# rocket-mega-shield.net
KiCad netlist of a schematic drawn in EAGLE
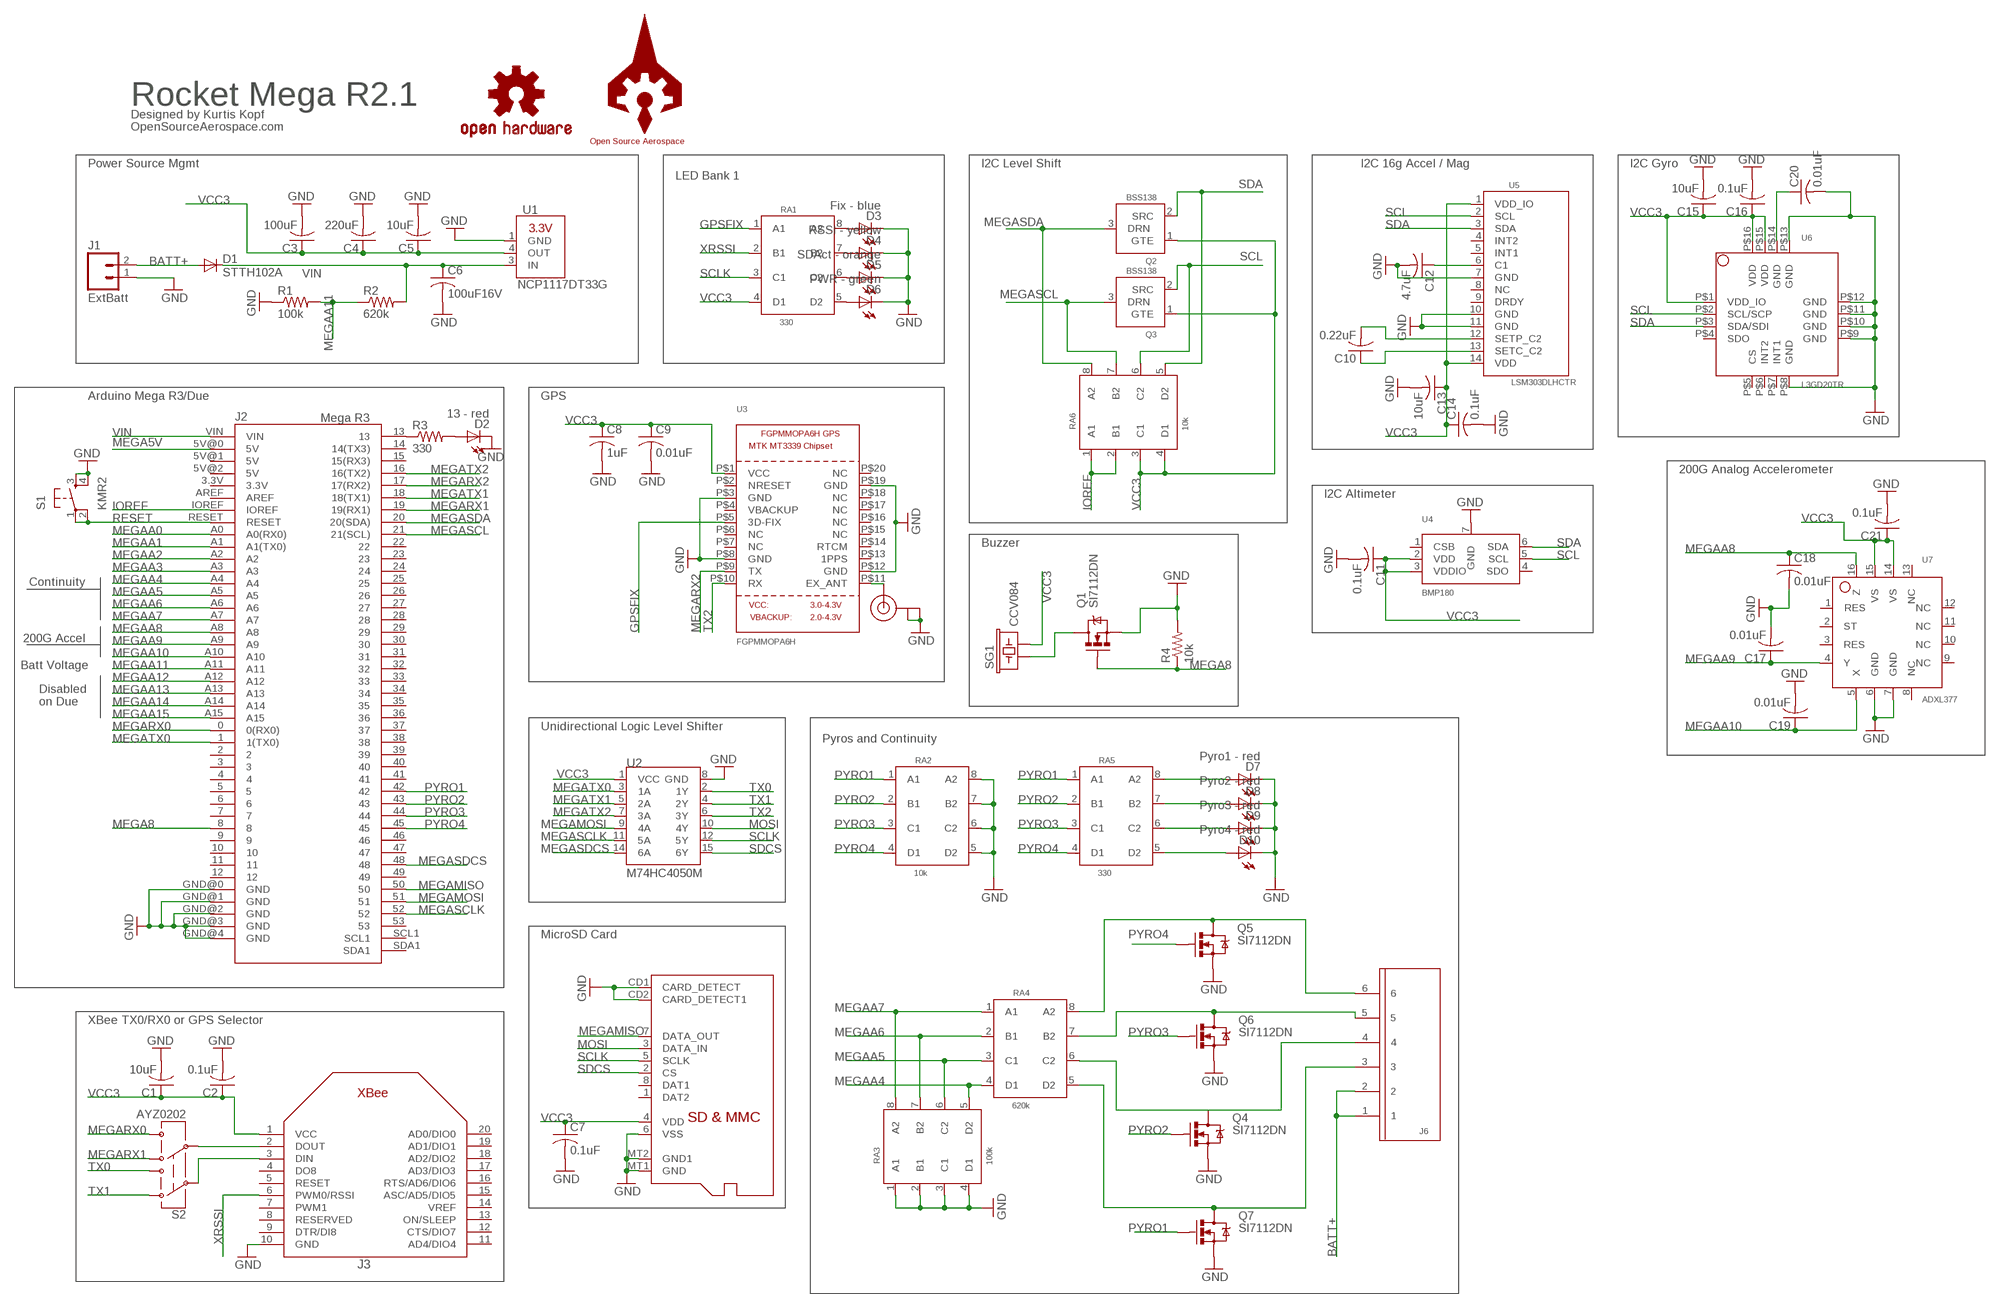
[diagram p0: schematic, sheet 1]

(export (version "E")
  (design (tool "Eeschema 10.0.6"))
  (components
    (comp (ref "C1")
      (value "10uF")
      (footprint "eagle-import:C1206")
      (libsource (lib "eagle-import") (part "C-USC1206"))
    )
    (comp (ref "C2")
      (value "0.1uF")
      (footprint "eagle-import:C1206")
      (libsource (lib "eagle-import") (part "C-USC1206"))
    )
    (comp (ref "C3")
      (value "100uF")
      (footprint "eagle-import:C1206")
      (libsource (lib "eagle-import") (part "C-USC1206"))
    )
    (comp (ref "C4")
      (value "220uF")
      (footprint "eagle-import:C1210")
      (libsource (lib "eagle-import") (part "C-USC1210"))
    )
    (comp (ref "C5")
      (value "10uF")
      (footprint "eagle-import:C1206")
      (libsource (lib "eagle-import") (part "C-USC1206"))
    )
    (comp (ref "C6")
      (value "100uF16V")
      (footprint "eagle-import:C1210")
      (libsource (lib "eagle-import") (part "C-USC1210"))
    )
    (comp (ref "C7")
      (value "0.1uF")
      (footprint "eagle-import:C1206")
      (libsource (lib "eagle-import") (part "C-USC1206"))
    )
    (comp (ref "C8")
      (value "1uF")
      (footprint "eagle-import:C1206")
      (libsource (lib "eagle-import") (part "C-USC1206"))
    )
    (comp (ref "C9")
      (value "0.01uF")
      (footprint "eagle-import:C1206")
      (libsource (lib "eagle-import") (part "C-USC1206"))
    )
    (comp (ref "C10")
      (value "0.22uF")
      (footprint "eagle-import:C1206")
      (libsource (lib "eagle-import") (part "C-USC1206"))
    )
    (comp (ref "C11")
      (value "0.1uF")
      (footprint "eagle-import:C1206")
      (libsource (lib "eagle-import") (part "C-USC1206"))
    )
    (comp (ref "C12")
      (value "4.7uF")
      (footprint "eagle-import:C1206")
      (libsource (lib "eagle-import") (part "C-USC1206"))
    )
    (comp (ref "C13")
      (value "10uF")
      (footprint "eagle-import:C1206")
      (libsource (lib "eagle-import") (part "C-USC1206"))
    )
    (comp (ref "C14")
      (value "0.1uF")
      (footprint "eagle-import:C1206")
      (libsource (lib "eagle-import") (part "C-USC1206"))
    )
    (comp (ref "C15")
      (value "10uF")
      (footprint "eagle-import:C1206")
      (libsource (lib "eagle-import") (part "C-USC1206"))
    )
    (comp (ref "C16")
      (value "0.1uF")
      (footprint "eagle-import:C1206")
      (libsource (lib "eagle-import") (part "C-USC1206"))
    )
    (comp (ref "C17")
      (value "0.01uF")
      (footprint "eagle-import:C1206")
      (libsource (lib "eagle-import") (part "C-USC1206"))
    )
    (comp (ref "C18")
      (value "0.01uF")
      (footprint "eagle-import:C1206")
      (libsource (lib "eagle-import") (part "C-USC1206"))
    )
    (comp (ref "C19")
      (value "0.01uF")
      (footprint "eagle-import:C1206")
      (libsource (lib "eagle-import") (part "C-USC1206"))
    )
    (comp (ref "C20")
      (value "0.01uF")
      (footprint "eagle-import:C1206")
      (libsource (lib "eagle-import") (part "C-USC1206"))
    )
    (comp (ref "C21")
      (value "0.1uF")
      (footprint "eagle-import:C1206")
      (libsource (lib "eagle-import") (part "C-USC1206"))
    )
    (comp (ref "D1")
      (value "STTH102A")
      (footprint "eagle-import:SMA-DIODE_ALT")
      (libsource (lib "eagle-import") (part "DIODESMA-ALT"))
    )
    (comp (ref "D2")
      (value "13 - red")
      (footprint "eagle-import:LED-1206")
      (libsource (lib "eagle-import") (part "LED1206"))
    )
    (comp (ref "D3")
      (value "Fix - blue")
      (footprint "eagle-import:LED-1206")
      (libsource (lib "eagle-import") (part "LED1206"))
    )
    (comp (ref "D4")
      (value "RSSI - yellow")
      (footprint "eagle-import:LED-1206")
      (libsource (lib "eagle-import") (part "LED1206"))
    )
    (comp (ref "D5")
      (value "SDAct - orange")
      (footprint "eagle-import:LED-1206")
      (libsource (lib "eagle-import") (part "LED1206"))
    )
    (comp (ref "D6")
      (value "PWR - green")
      (footprint "eagle-import:LED-1206")
      (libsource (lib "eagle-import") (part "LED1206"))
    )
    (comp (ref "D7")
      (value "Pyro1 - red")
      (footprint "eagle-import:LED-1206")
      (libsource (lib "eagle-import") (part "LED1206"))
    )
    (comp (ref "D8")
      (value "Pyro2 - red")
      (footprint "eagle-import:LED-1206")
      (libsource (lib "eagle-import") (part "LED1206"))
    )
    (comp (ref "D9")
      (value "Pyro3 - red")
      (footprint "eagle-import:LED-1206")
      (libsource (lib "eagle-import") (part "LED1206"))
    )
    (comp (ref "D10")
      (value "Pyro4 - red")
      (footprint "eagle-import:LED-1206")
      (libsource (lib "eagle-import") (part "LED1206"))
    )
    (comp (ref "J1")
      (value "ExtBatt")
      (footprint "eagle-import:JST-2-PTH-NS")
      (libsource (lib "eagle-import") (part "M02-JST-2-PTH-NO_SILK"))
    )
    (comp (ref "J2")
      (value "Mega R3")
      (footprint "eagle-import:ARDUINO_MEGA")
      (libsource (lib "eagle-import") (part "ARDUINO-MEGAFULL"))
    )
    (comp (ref "J3")
      (value "XBEE")
      (footprint "eagle-import:XBEE")
      (libsource (lib "eagle-import") (part "XBEE"))
    )
    (comp (ref "J4")
      (value "MICROSD")
      (footprint "eagle-import:MICROSD")
      (libsource (lib "eagle-import") (part "MICROSD"))
    )
    (comp (ref "J5")
      (value "U.FL")
      (footprint "eagle-import:U.FL")
      (libsource (lib "eagle-import") (part "U.FL"))
    )
    (comp (ref "J6")
      (value "1X6TERMINALBLOCK")
      (footprint "eagle-import:1X6TERMINALBLOCK")
      (libsource (lib "eagle-import") (part "1X6TERMINALBLOCK"))
    )
    (comp (ref "LOGO1")
      (value "OSHW-LOGOM")
      (footprint "eagle-import:OSHW-LOGO-M")
      (libsource (lib "eagle-import") (part "OSHW-LOGOM"))
    )
    (comp (ref "Q1")
      (value "SI7112DN")
      (footprint "eagle-import:POWERPAK1212-8")
      (libsource (lib "eagle-import") (part "MOSFET-NCHANNELSI7820DN"))
    )
    (comp (ref "Q2")
      (value "BSS138")
      (footprint "eagle-import:SOT23")
      (libsource (lib "eagle-import") (part "BSS138"))
    )
    (comp (ref "Q3")
      (value "BSS138")
      (footprint "eagle-import:SOT23")
      (libsource (lib "eagle-import") (part "BSS138"))
    )
    (comp (ref "Q4")
      (value "SI7112DN")
      (footprint "eagle-import:POWERPAK1212-8")
      (libsource (lib "eagle-import") (part "MOSFET-NCHANNELSI7820DN"))
    )
    (comp (ref "Q5")
      (value "SI7112DN")
      (footprint "eagle-import:POWERPAK1212-8")
      (libsource (lib "eagle-import") (part "MOSFET-NCHANNELSI7820DN"))
    )
    (comp (ref "Q6")
      (value "SI7112DN")
      (footprint "eagle-import:POWERPAK1212-8")
      (libsource (lib "eagle-import") (part "MOSFET-NCHANNELSI7820DN"))
    )
    (comp (ref "Q7")
      (value "SI7112DN")
      (footprint "eagle-import:POWERPAK1212-8")
      (libsource (lib "eagle-import") (part "MOSFET-NCHANNELSI7820DN"))
    )
    (comp (ref "R1")
      (value "100k")
      (footprint "eagle-import:R1206")
      (libsource (lib "eagle-import") (part "R-US_R1206"))
    )
    (comp (ref "R2")
      (value "620k")
      (footprint "eagle-import:R1206")
      (libsource (lib "eagle-import") (part "R-US_R1206"))
    )
    (comp (ref "R3")
      (value "330")
      (footprint "eagle-import:R1206")
      (libsource (lib "eagle-import") (part "R-US_R1206"))
    )
    (comp (ref "R4")
      (value "10k")
      (footprint "eagle-import:R1206")
      (libsource (lib "eagle-import") (part "R-US_R1206"))
    )
    (comp (ref "RA1")
      (value "330")
      (footprint "eagle-import:1206X4RESISTORARRAY")
      (libsource (lib "eagle-import") (part "RESISTOR_CRA06S08"))
    )
    (comp (ref "RA2")
      (value "10k")
      (footprint "eagle-import:1206X4RESISTORARRAY")
      (libsource (lib "eagle-import") (part "RESISTOR_CRA06S08"))
    )
    (comp (ref "RA3")
      (value "100k")
      (footprint "eagle-import:1206X4RESISTORARRAY")
      (libsource (lib "eagle-import") (part "RESISTOR_CRA06S08"))
    )
    (comp (ref "RA4")
      (value "620k")
      (footprint "eagle-import:1206X4RESISTORARRAY")
      (libsource (lib "eagle-import") (part "RESISTOR_CRA06S08"))
    )
    (comp (ref "RA5")
      (value "330")
      (footprint "eagle-import:1206X4RESISTORARRAY")
      (libsource (lib "eagle-import") (part "RESISTOR_CRA06S08"))
    )
    (comp (ref "RA6")
      (value "10k")
      (footprint "eagle-import:1206X4RESISTORARRAY")
      (libsource (lib "eagle-import") (part "RESISTOR_CRA06S08"))
    )
    (comp (ref "S1")
      (value "KMR2")
      (footprint "eagle-import:TACTILE_KMR2")
      (libsource (lib "eagle-import") (part "TAC_SWITCHKMR2"))
    )
    (comp (ref "S2")
      (value "AYZ0202")
      (footprint "eagle-import:AYZ0202")
      (libsource (lib "eagle-import") (part "AYZ0202"))
    )
    (comp (ref "SG1")
      (value "CCV084")
      (footprint "eagle-import:BUZZER-CCV")
      (libsource (lib "eagle-import") (part "BUZZERSMD2"))
    )
    (comp (ref "U$1")
      (value "OSAEROSPACEVECTOR")
      (footprint "eagle-import:OSAEROSPACE_V")
      (libsource (lib "eagle-import") (part "OSAEROSPACEVECTOR"))
    )
    (comp (ref "U1")
      (value "NCP1117DT33G")
      (footprint "eagle-import:DPAK")
      (libsource (lib "eagle-import") (part "NCP1117DT33G"))
    )
    (comp (ref "U2")
      (value "M74HC4050M")
      (footprint "eagle-import:SO016")
      (libsource (lib "eagle-import") (part "HEX_CONVERTER"))
    )
    (comp (ref "U3")
      (value "FGPMMOPA6H")
      (footprint "eagle-import:FGPMMOPA6H")
      (libsource (lib "eagle-import") (part "GPS_FGPMMOPA6H"))
    )
    (comp (ref "U4")
      (value "BMP180")
      (footprint "eagle-import:BMP180")
      (libsource (lib "eagle-import") (part "BMP180"))
    )
    (comp (ref "U5")
      (value "LSM303DLHCTR")
      (footprint "eagle-import:LGA14")
      (libsource (lib "eagle-import") (part "LSM303DLHC"))
    )
    (comp (ref "U6")
      (value "L3GD20TR")
      (footprint "eagle-import:LGA16-4X4")
      (libsource (lib "eagle-import") (part "L3GD20"))
    )
    (comp (ref "U7")
      (value "ADXL377")
      (footprint "eagle-import:LFCSP-16")
      (libsource (lib "eagle-import") (part "ADXL377"))
    )
  )
  (nets
    (net (code "1") (name "/BATT+") (class "Default")
      (node (ref "D1") (pin "A") (pinfunction "A_A") (pintype "passive"))
      (node (ref "J1") (pin "2") (pinfunction "2_2") (pintype "passive"))
      (node (ref "J6") (pin "1") (pinfunction "1_1") (pintype "bidirectional"))
      (node (ref "J6") (pin "2") (pinfunction "2_2") (pintype "bidirectional"))
    )
    (net (code "2") (name "/GPSFIX") (class "Default")
      (node (ref "RA1") (pin "1") (pinfunction "A1_1") (pintype "passive"))
      (node (ref "U3") (pin "P$5") (pinfunction "3D-FIX_P$5") (pintype "bidirectional"))
    )
    (net (code "3") (name "/IOREF") (class "Default")
      (node (ref "J2") (pin "IOREF") (pinfunction "IOREF_IOREF") (pintype "bidirectional"))
      (node (ref "RA6") (pin "1") (pinfunction "A1_1") (pintype "passive"))
      (node (ref "RA6") (pin "2") (pinfunction "B1_2") (pintype "passive"))
    )
    (net (code "4") (name "/MEGA5V") (class "Default")
      (node (ref "J2") (pin "5V@0") (pinfunction "5V_5V@0") (pintype "bidirectional"))
    )
    (net (code "5") (name "/MEGA8") (class "Default")
      (node (ref "J2") (pin "8") (pinfunction "8_8") (pintype "bidirectional"))
      (node (ref "Q1") (pin "G") (pinfunction "G_G") (pintype "passive"))
      (node (ref "R4") (pin "1") (pinfunction "1_1") (pintype "passive"))
    )
    (net (code "6") (name "/MEGAA0") (class "Default")
      (node (ref "J2") (pin "A0") (pinfunction "A0(RX0)_A0") (pintype "bidirectional"))
    )
    (net (code "7") (name "/MEGAA1") (class "Default")
      (node (ref "J2") (pin "A1") (pinfunction "A1(TX0)_A1") (pintype "bidirectional"))
    )
    (net (code "8") (name "/MEGAA2") (class "Default")
      (node (ref "J2") (pin "A2") (pinfunction "A2_A2") (pintype "bidirectional"))
    )
    (net (code "9") (name "/MEGAA3") (class "Default")
      (node (ref "J2") (pin "A3") (pinfunction "A3_A3") (pintype "bidirectional"))
    )
    (net (code "10") (name "/MEGAA4") (class "Default")
      (node (ref "J2") (pin "A4") (pinfunction "A4_A4") (pintype "bidirectional"))
      (node (ref "RA3") (pin "5") (pinfunction "D2_5") (pintype "passive"))
      (node (ref "RA4") (pin "4") (pinfunction "D1_4") (pintype "passive"))
    )
    (net (code "11") (name "/MEGAA5") (class "Default")
      (node (ref "J2") (pin "A5") (pinfunction "A5_A5") (pintype "bidirectional"))
      (node (ref "RA3") (pin "6") (pinfunction "C2_6") (pintype "passive"))
      (node (ref "RA4") (pin "3") (pinfunction "C1_3") (pintype "passive"))
    )
    (net (code "12") (name "/MEGAA6") (class "Default")
      (node (ref "J2") (pin "A6") (pinfunction "A6_A6") (pintype "bidirectional"))
      (node (ref "RA3") (pin "7") (pinfunction "B2_7") (pintype "passive"))
      (node (ref "RA4") (pin "2") (pinfunction "B1_2") (pintype "passive"))
    )
    (net (code "13") (name "/MEGAA7") (class "Default")
      (node (ref "J2") (pin "A7") (pinfunction "A7_A7") (pintype "bidirectional"))
      (node (ref "RA3") (pin "8") (pinfunction "A2_8") (pintype "passive"))
      (node (ref "RA4") (pin "1") (pinfunction "A1_1") (pintype "passive"))
    )
    (net (code "14") (name "/MEGAA8") (class "Default")
      (node (ref "C18") (pin "1") (pinfunction "1_1") (pintype "passive"))
      (node (ref "J2") (pin "A8") (pinfunction "A8_A8") (pintype "bidirectional"))
      (node (ref "U7") (pin "16") (pinfunction "Z_16") (pintype "output"))
    )
    (net (code "15") (name "/MEGAA9") (class "Default")
      (node (ref "C17") (pin "1") (pinfunction "1_1") (pintype "passive"))
      (node (ref "J2") (pin "A9") (pinfunction "A9_A9") (pintype "bidirectional"))
      (node (ref "U7") (pin "4") (pinfunction "Y_4") (pintype "output"))
    )
    (net (code "16") (name "/MEGAA10") (class "Default")
      (node (ref "C19") (pin "1") (pinfunction "1_1") (pintype "passive"))
      (node (ref "J2") (pin "A10") (pinfunction "A10_A10") (pintype "bidirectional"))
      (node (ref "U7") (pin "5") (pinfunction "X_5") (pintype "output"))
    )
    (net (code "17") (name "/MEGAA11") (class "Default")
      (node (ref "J2") (pin "A11") (pinfunction "A11_A11") (pintype "bidirectional"))
      (node (ref "R1") (pin "2") (pinfunction "2_2") (pintype "passive"))
      (node (ref "R2") (pin "1") (pinfunction "1_1") (pintype "passive"))
    )
    (net (code "18") (name "/MEGAA12") (class "Default")
      (node (ref "J2") (pin "A12") (pinfunction "A12_A12") (pintype "bidirectional"))
    )
    (net (code "19") (name "/MEGAA13") (class "Default")
      (node (ref "J2") (pin "A13") (pinfunction "A13_A13") (pintype "bidirectional"))
    )
    (net (code "20") (name "/MEGAA14") (class "Default")
      (node (ref "J2") (pin "A14") (pinfunction "A14_A14") (pintype "bidirectional"))
    )
    (net (code "21") (name "/MEGAA15") (class "Default")
      (node (ref "J2") (pin "A15") (pinfunction "A15_A15") (pintype "bidirectional"))
    )
    (net (code "22") (name "/MEGAMISO") (class "Default")
      (node (ref "J2") (pin "50") (pinfunction "50_50") (pintype "bidirectional"))
      (node (ref "J4") (pin "7") (pinfunction "DATA_OUT_7") (pintype "output"))
    )
    (net (code "23") (name "/MEGAMOSI") (class "Default")
      (node (ref "J2") (pin "51") (pinfunction "51_51") (pintype "bidirectional"))
      (node (ref "U2") (pin "9") (pinfunction "4A_9") (pintype "bidirectional"))
    )
    (net (code "24") (name "/MEGARX0") (class "Default")
      (node (ref "J2") (pin "0") (pinfunction "0(RX0)_0") (pintype "bidirectional"))
      (node (ref "S2") (pin "4") (pinfunction "6_4") (pintype "bidirectional"))
    )
    (net (code "25") (name "/MEGARX1") (class "Default")
      (node (ref "J2") (pin "19") (pinfunction "19(RX1)_19") (pintype "bidirectional"))
      (node (ref "S2") (pin "6") (pinfunction "4_6") (pintype "bidirectional"))
    )
    (net (code "26") (name "/MEGARX2") (class "Default")
      (node (ref "J2") (pin "17") (pinfunction "17(RX2)_17") (pintype "bidirectional"))
      (node (ref "U3") (pin "P$9") (pinfunction "TX_P$9") (pintype "bidirectional"))
    )
    (net (code "27") (name "/MEGASCL") (class "Default")
      (node (ref "J2") (pin "21") (pinfunction "21(SCL)_21") (pintype "bidirectional"))
      (node (ref "Q3") (pin "3") (pinfunction "DRN_3") (pintype "bidirectional"))
      (node (ref "RA6") (pin "7") (pinfunction "B2_7") (pintype "passive"))
    )
    (net (code "28") (name "/MEGASCLK") (class "Default")
      (node (ref "J2") (pin "52") (pinfunction "52_52") (pintype "bidirectional"))
      (node (ref "U2") (pin "11") (pinfunction "5A_11") (pintype "bidirectional"))
    )
    (net (code "29") (name "/MEGASDA") (class "Default")
      (node (ref "J2") (pin "20") (pinfunction "20(SDA)_20") (pintype "bidirectional"))
      (node (ref "Q2") (pin "3") (pinfunction "DRN_3") (pintype "bidirectional"))
      (node (ref "RA6") (pin "8") (pinfunction "A2_8") (pintype "passive"))
    )
    (net (code "30") (name "/MEGASDCS") (class "Default")
      (node (ref "J2") (pin "48") (pinfunction "48_48") (pintype "bidirectional"))
      (node (ref "U2") (pin "14") (pinfunction "6A_14") (pintype "bidirectional"))
    )
    (net (code "31") (name "/MEGATX0") (class "Default")
      (node (ref "J2") (pin "1") (pinfunction "1(TX0)_1") (pintype "bidirectional"))
      (node (ref "U2") (pin "3") (pinfunction "1A_3") (pintype "bidirectional"))
    )
    (net (code "32") (name "/MEGATX1") (class "Default")
      (node (ref "J2") (pin "18") (pinfunction "18(TX1)_18") (pintype "bidirectional"))
      (node (ref "U2") (pin "5") (pinfunction "2A_5") (pintype "bidirectional"))
    )
    (net (code "33") (name "/MEGATX2") (class "Default")
      (node (ref "J2") (pin "16") (pinfunction "16(TX2)_16") (pintype "bidirectional"))
      (node (ref "U2") (pin "7") (pinfunction "3A_7") (pintype "bidirectional"))
    )
    (net (code "34") (name "/MOSI") (class "Default")
      (node (ref "J4") (pin "3") (pinfunction "DATA_IN_3") (pintype "input"))
      (node (ref "U2") (pin "10") (pinfunction "4Y_10") (pintype "bidirectional"))
    )
    (net (code "35") (name "/PYRO1") (class "Default")
      (node (ref "J2") (pin "42") (pinfunction "42_42") (pintype "bidirectional"))
      (node (ref "Q7") (pin "G") (pinfunction "G_G") (pintype "passive"))
      (node (ref "RA2") (pin "1") (pinfunction "A1_1") (pintype "passive"))
      (node (ref "RA5") (pin "1") (pinfunction "A1_1") (pintype "passive"))
    )
    (net (code "36") (name "/PYRO2") (class "Default")
      (node (ref "J2") (pin "43") (pinfunction "43_43") (pintype "bidirectional"))
      (node (ref "Q4") (pin "G") (pinfunction "G_G") (pintype "passive"))
      (node (ref "RA2") (pin "2") (pinfunction "B1_2") (pintype "passive"))
      (node (ref "RA5") (pin "2") (pinfunction "B1_2") (pintype "passive"))
    )
    (net (code "37") (name "/PYRO3") (class "Default")
      (node (ref "J2") (pin "44") (pinfunction "44_44") (pintype "bidirectional"))
      (node (ref "Q6") (pin "G") (pinfunction "G_G") (pintype "passive"))
      (node (ref "RA2") (pin "3") (pinfunction "C1_3") (pintype "passive"))
      (node (ref "RA5") (pin "3") (pinfunction "C1_3") (pintype "passive"))
    )
    (net (code "38") (name "/PYRO4") (class "Default")
      (node (ref "J2") (pin "45") (pinfunction "45_45") (pintype "bidirectional"))
      (node (ref "Q5") (pin "G") (pinfunction "G_G") (pintype "passive"))
      (node (ref "RA2") (pin "4") (pinfunction "D1_4") (pintype "passive"))
      (node (ref "RA5") (pin "4") (pinfunction "D1_4") (pintype "passive"))
    )
    (net (code "39") (name "/RESET") (class "Default")
      (node (ref "J2") (pin "RESET") (pinfunction "RESET_RESET") (pintype "bidirectional"))
      (node (ref "S1") (pin "1") (pinfunction "1_1") (pintype "passive"))
      (node (ref "S1") (pin "2") (pinfunction "2_2") (pintype "passive"))
    )
    (net (code "40") (name "/SCL") (class "Default")
      (node (ref "Q3") (pin "2") (pinfunction "SRC_2") (pintype "bidirectional"))
      (node (ref "RA6") (pin "6") (pinfunction "C2_6") (pintype "passive"))
      (node (ref "U4") (pin "5") (pinfunction "SCL_5") (pintype "bidirectional"))
      (node (ref "U5") (pin "2") (pinfunction "SCL_2") (pintype "bidirectional"))
      (node (ref "U6") (pin "P$2") (pinfunction "SCL/SCP_P$2") (pintype "bidirectional"))
    )
    (net (code "41") (name "/SCLK") (class "Default")
      (node (ref "J4") (pin "5") (pinfunction "SCLK_5") (pintype "input"))
      (node (ref "RA1") (pin "3") (pinfunction "C1_3") (pintype "passive"))
      (node (ref "U2") (pin "12") (pinfunction "5Y_12") (pintype "bidirectional"))
    )
    (net (code "42") (name "/SDA") (class "Default")
      (node (ref "Q2") (pin "2") (pinfunction "SRC_2") (pintype "bidirectional"))
      (node (ref "RA6") (pin "5") (pinfunction "D2_5") (pintype "passive"))
      (node (ref "U4") (pin "6") (pinfunction "SDA_6") (pintype "bidirectional"))
      (node (ref "U5") (pin "3") (pinfunction "SDA_3") (pintype "bidirectional"))
      (node (ref "U6") (pin "P$3") (pinfunction "SDA/SDI_P$3") (pintype "bidirectional"))
    )
    (net (code "43") (name "/SDCS") (class "Default")
      (node (ref "J4") (pin "2") (pinfunction "CS_2") (pintype "input"))
      (node (ref "U2") (pin "15") (pinfunction "6Y_15") (pintype "bidirectional"))
    )
    (net (code "44") (name "/TX0") (class "Default")
      (node (ref "S2") (pin "1") (pinfunction "3_1") (pintype "bidirectional"))
      (node (ref "U2") (pin "2") (pinfunction "1Y_2") (pintype "bidirectional"))
    )
    (net (code "45") (name "/TX1") (class "Default")
      (node (ref "S2") (pin "3") (pinfunction "1_3") (pintype "bidirectional"))
      (node (ref "U2") (pin "4") (pinfunction "2Y_4") (pintype "bidirectional"))
    )
    (net (code "46") (name "/TX2") (class "Default")
      (node (ref "U2") (pin "6") (pinfunction "3Y_6") (pintype "bidirectional"))
      (node (ref "U3") (pin "P$10") (pinfunction "RX_P$10") (pintype "bidirectional"))
    )
    (net (code "47") (name "/VCC3") (class "Default")
      (node (ref "C1") (pin "1") (pinfunction "1_1") (pintype "passive"))
      (node (ref "C11") (pin "1") (pinfunction "1_1") (pintype "passive"))
      (node (ref "C13") (pin "1") (pinfunction "1_1") (pintype "passive"))
      (node (ref "C14") (pin "1") (pinfunction "1_1") (pintype "passive"))
      (node (ref "C15") (pin "1") (pinfunction "1_1") (pintype "passive"))
      (node (ref "C16") (pin "1") (pinfunction "1_1") (pintype "passive"))
      (node (ref "C2") (pin "1") (pinfunction "1_1") (pintype "passive"))
      (node (ref "C21") (pin "1") (pinfunction "1_1") (pintype "passive"))
      (node (ref "C3") (pin "1") (pinfunction "1_1") (pintype "passive"))
      (node (ref "C4") (pin "1") (pinfunction "1_1") (pintype "passive"))
      (node (ref "C5") (pin "1") (pinfunction "1_1") (pintype "passive"))
      (node (ref "C7") (pin "1") (pinfunction "1_1") (pintype "passive"))
      (node (ref "C8") (pin "1") (pinfunction "1_1") (pintype "passive"))
      (node (ref "C9") (pin "1") (pinfunction "1_1") (pintype "passive"))
      (node (ref "J3") (pin "1") (pinfunction "VCC_1") (pintype "power_in"))
      (node (ref "J4") (pin "4") (pinfunction "VDD_4") (pintype "power_in"))
      (node (ref "Q2") (pin "1") (pinfunction "GTE_1") (pintype "bidirectional"))
      (node (ref "Q3") (pin "1") (pinfunction "GTE_1") (pintype "bidirectional"))
      (node (ref "RA1") (pin "4") (pinfunction "D1_4") (pintype "passive"))
      (node (ref "RA6") (pin "3") (pinfunction "C1_3") (pintype "passive"))
      (node (ref "RA6") (pin "4") (pinfunction "D1_4") (pintype "passive"))
      (node (ref "SG1") (pin "-") (pinfunction "2_-") (pintype "passive"))
      (node (ref "U1") (pin "4") (pinfunction "OUT_4") (pintype "power_in"))
      (node (ref "U2") (pin "1") (pinfunction "VCC_1") (pintype "bidirectional"))
      (node (ref "U3") (pin "P$1") (pinfunction "VCC_P$1") (pintype "bidirectional"))
      (node (ref "U4") (pin "2") (pinfunction "VDD_2") (pintype "power_in"))
      (node (ref "U4") (pin "3") (pinfunction "VDDIO_3") (pintype "power_in"))
      (node (ref "U5") (pin "1") (pinfunction "VDD_IO_1") (pintype "power_in"))
      (node (ref "U5") (pin "14") (pinfunction "VDD_14") (pintype "power_in"))
      (node (ref "U6") (pin "P$1") (pinfunction "VDD_IO_P$1") (pintype "power_in"))
      (node (ref "U6") (pin "P$15") (pinfunction "VDD_P$15") (pintype "power_in"))
      (node (ref "U6") (pin "P$16") (pinfunction "VDD_P$16") (pintype "power_in"))
      (node (ref "U7") (pin "14") (pinfunction "VS_14") (pintype "power_in"))
      (node (ref "U7") (pin "15") (pinfunction "VS_15") (pintype "power_in"))
    )
    (net (code "48") (name "/VIN") (class "Default")
      (node (ref "C6") (pin "1") (pinfunction "1_1") (pintype "passive"))
      (node (ref "D1") (pin "C") (pinfunction "C_C") (pintype "passive"))
      (node (ref "J2") (pin "VIN") (pinfunction "VIN_VIN") (pintype "bidirectional"))
      (node (ref "R2") (pin "2") (pinfunction "2_2") (pintype "passive"))
      (node (ref "U1") (pin "3") (pinfunction "IN_3") (pintype "power_in"))
    )
    (net (code "49") (name "/XRSSI") (class "Default")
      (node (ref "J3") (pin "6") (pinfunction "PWM0/RSSI_6") (pintype "output"))
      (node (ref "RA1") (pin "2") (pinfunction "B1_2") (pintype "passive"))
    )
    (net (code "50") (name "GND") (class "Default")
      (node (ref "C1") (pin "2") (pinfunction "2_2") (pintype "passive"))
      (node (ref "C11") (pin "2") (pinfunction "2_2") (pintype "passive"))
      (node (ref "C12") (pin "2") (pinfunction "2_2") (pintype "passive"))
      (node (ref "C13") (pin "2") (pinfunction "2_2") (pintype "passive"))
      (node (ref "C14") (pin "2") (pinfunction "2_2") (pintype "passive"))
      (node (ref "C15") (pin "2") (pinfunction "2_2") (pintype "passive"))
      (node (ref "C16") (pin "2") (pinfunction "2_2") (pintype "passive"))
      (node (ref "C17") (pin "2") (pinfunction "2_2") (pintype "passive"))
      (node (ref "C18") (pin "2") (pinfunction "2_2") (pintype "passive"))
      (node (ref "C19") (pin "2") (pinfunction "2_2") (pintype "passive"))
      (node (ref "C2") (pin "2") (pinfunction "2_2") (pintype "passive"))
      (node (ref "C20") (pin "2") (pinfunction "2_2") (pintype "passive"))
      (node (ref "C21") (pin "2") (pinfunction "2_2") (pintype "passive"))
      (node (ref "C3") (pin "2") (pinfunction "2_2") (pintype "passive"))
      (node (ref "C4") (pin "2") (pinfunction "2_2") (pintype "passive"))
      (node (ref "C5") (pin "2") (pinfunction "2_2") (pintype "passive"))
      (node (ref "C6") (pin "2") (pinfunction "2_2") (pintype "passive"))
      (node (ref "C7") (pin "2") (pinfunction "2_2") (pintype "passive"))
      (node (ref "C8") (pin "2") (pinfunction "2_2") (pintype "passive"))
      (node (ref "C9") (pin "2") (pinfunction "2_2") (pintype "passive"))
      (node (ref "D10") (pin "C") (pinfunction "C_C") (pintype "passive"))
      (node (ref "D2") (pin "C") (pinfunction "C_C") (pintype "passive"))
      (node (ref "D3") (pin "C") (pinfunction "C_C") (pintype "passive"))
      (node (ref "D4") (pin "C") (pinfunction "C_C") (pintype "passive"))
      (node (ref "D5") (pin "C") (pinfunction "C_C") (pintype "passive"))
      (node (ref "D6") (pin "C") (pinfunction "C_C") (pintype "passive"))
      (node (ref "D7") (pin "C") (pinfunction "C_C") (pintype "passive"))
      (node (ref "D8") (pin "C") (pinfunction "C_C") (pintype "passive"))
      (node (ref "D9") (pin "C") (pinfunction "C_C") (pintype "passive"))
      (node (ref "J1") (pin "1") (pinfunction "1_1") (pintype "passive"))
      (node (ref "J2") (pin "GND@0") (pinfunction "GND_GND@0") (pintype "bidirectional"))
      (node (ref "J2") (pin "GND@1") (pinfunction "GND_GND@1") (pintype "bidirectional"))
      (node (ref "J2") (pin "GND@2") (pinfunction "GND_GND@2") (pintype "bidirectional"))
      (node (ref "J2") (pin "GND@3") (pinfunction "GND_GND@3") (pintype "bidirectional"))
      (node (ref "J2") (pin "GND@4") (pinfunction "GND_GND@4") (pintype "bidirectional"))
      (node (ref "J3") (pin "10") (pinfunction "GND_10") (pintype "power_in"))
      (node (ref "J4") (pin "6") (pinfunction "VSS_6") (pintype "power_in"))
      (node (ref "J4") (pin "CD1") (pinfunction "CARD_DETECT_CD1") (pintype "passive"))
      (node (ref "J4") (pin "CD2") (pinfunction "CARD_DETECT1_CD2") (pintype "passive"))
      (node (ref "J4") (pin "MT1") (pinfunction "GND_MT1") (pintype "power_in"))
      (node (ref "J4") (pin "MT2") (pinfunction "GND1_MT2") (pintype "power_in"))
      (node (ref "J5") (pin "P$1") (pinfunction "GND_P$1") (pintype "bidirectional"))
      (node (ref "J5") (pin "P$2") (pinfunction "GND_P$2") (pintype "bidirectional"))
      (node (ref "Q1") (pin "S1") (pinfunction "S_S1") (pintype "passive"))
      (node (ref "Q1") (pin "S2") (pinfunction "S_S2") (pintype "passive"))
      (node (ref "Q1") (pin "S3") (pinfunction "S_S3") (pintype "passive"))
      (node (ref "Q4") (pin "S1") (pinfunction "S_S1") (pintype "passive"))
      (node (ref "Q4") (pin "S2") (pinfunction "S_S2") (pintype "passive"))
      (node (ref "Q4") (pin "S3") (pinfunction "S_S3") (pintype "passive"))
      (node (ref "Q5") (pin "S1") (pinfunction "S_S1") (pintype "passive"))
      (node (ref "Q5") (pin "S2") (pinfunction "S_S2") (pintype "passive"))
      (node (ref "Q5") (pin "S3") (pinfunction "S_S3") (pintype "passive"))
      (node (ref "Q6") (pin "S1") (pinfunction "S_S1") (pintype "passive"))
      (node (ref "Q6") (pin "S2") (pinfunction "S_S2") (pintype "passive"))
      (node (ref "Q6") (pin "S3") (pinfunction "S_S3") (pintype "passive"))
      (node (ref "Q7") (pin "S1") (pinfunction "S_S1") (pintype "passive"))
      (node (ref "Q7") (pin "S2") (pinfunction "S_S2") (pintype "passive"))
      (node (ref "Q7") (pin "S3") (pinfunction "S_S3") (pintype "passive"))
      (node (ref "R1") (pin "1") (pinfunction "1_1") (pintype "passive"))
      (node (ref "R4") (pin "2") (pinfunction "2_2") (pintype "passive"))
      (node (ref "RA2") (pin "5") (pinfunction "D2_5") (pintype "passive"))
      (node (ref "RA2") (pin "6") (pinfunction "C2_6") (pintype "passive"))
      (node (ref "RA2") (pin "7") (pinfunction "B2_7") (pintype "passive"))
      (node (ref "RA2") (pin "8") (pinfunction "A2_8") (pintype "passive"))
      (node (ref "RA3") (pin "1") (pinfunction "A1_1") (pintype "passive"))
      (node (ref "RA3") (pin "2") (pinfunction "B1_2") (pintype "passive"))
      (node (ref "RA3") (pin "3") (pinfunction "C1_3") (pintype "passive"))
      (node (ref "RA3") (pin "4") (pinfunction "D1_4") (pintype "passive"))
      (node (ref "S1") (pin "3") (pinfunction "3_3") (pintype "passive"))
      (node (ref "S1") (pin "4") (pinfunction "4_4") (pintype "passive"))
      (node (ref "U1") (pin "1") (pinfunction "GND_1") (pintype "power_in"))
      (node (ref "U2") (pin "8") (pinfunction "GND_8") (pintype "bidirectional"))
      (node (ref "U3") (pin "P$12") (pinfunction "GND_P$12") (pintype "bidirectional"))
      (node (ref "U3") (pin "P$19") (pinfunction "GND_P$19") (pintype "bidirectional"))
      (node (ref "U3") (pin "P$3") (pinfunction "GND_P$3") (pintype "bidirectional"))
      (node (ref "U3") (pin "P$8") (pinfunction "GND_P$8") (pintype "bidirectional"))
      (node (ref "U4") (pin "7") (pinfunction "GND_7") (pintype "power_in"))
      (node (ref "U5") (pin "10") (pinfunction "GND_10") (pintype "power_in"))
      (node (ref "U5") (pin "11") (pinfunction "GND_11") (pintype "power_in"))
      (node (ref "U5") (pin "7") (pinfunction "GND_7") (pintype "power_in"))
      (node (ref "U6") (pin "P$10") (pinfunction "GND_P$10") (pintype "power_in"))
      (node (ref "U6") (pin "P$11") (pinfunction "GND_P$11") (pintype "power_in"))
      (node (ref "U6") (pin "P$12") (pinfunction "GND_P$12") (pintype "power_in"))
      (node (ref "U6") (pin "P$13") (pinfunction "GND_P$13") (pintype "power_in"))
      (node (ref "U6") (pin "P$8") (pinfunction "GND_P$8") (pintype "power_in"))
      (node (ref "U6") (pin "P$9") (pinfunction "GND_P$9") (pintype "power_in"))
      (node (ref "U7") (pin "6") (pinfunction "GND_6") (pintype "power_in"))
      (node (ref "U7") (pin "7") (pinfunction "GND_7") (pintype "power_in"))
    )
    (net (code "51") (name "Net-(C20-Pad1)") (class "Default")
      (node (ref "C20") (pin "1") (pinfunction "1_1") (pintype "passive"))
      (node (ref "U6") (pin "P$14") (pinfunction "GND_P$14") (pintype "power_in"))
    )
    (net (code "52") (name "Net-(D2-PadA)") (class "Default")
      (node (ref "D2") (pin "A") (pinfunction "A_A") (pintype "passive"))
      (node (ref "R3") (pin "2") (pinfunction "2_2") (pintype "passive"))
    )
    (net (code "53") (name "Net-(J2-Pad13)") (class "Default")
      (node (ref "J2") (pin "13") (pinfunction "13_13") (pintype "bidirectional"))
      (node (ref "R3") (pin "1") (pinfunction "1_1") (pintype "passive"))
    )
    (net (code "54") (name "Net-(J3-DIN)") (class "Default")
      (node (ref "J3") (pin "3") (pinfunction "DIN_3") (pintype "input"))
      (node (ref "S2") (pin "2") (pinfunction "2_2") (pintype "bidirectional"))
    )
    (net (code "55") (name "Net-(J3-DOUT)") (class "Default")
      (node (ref "J3") (pin "2") (pinfunction "DOUT_2") (pintype "output"))
      (node (ref "S2") (pin "5") (pinfunction "5_5") (pintype "bidirectional"))
    )
    (net (code "56") (name "Net-(J5-SIGNAL)") (class "Default")
      (node (ref "J5") (pin "P$3") (pinfunction "SIGNAL_P$3") (pintype "bidirectional"))
      (node (ref "U3") (pin "P$11") (pinfunction "EX_ANT_P$11") (pintype "bidirectional"))
    )
    (net (code "57") (name "Net-(RA1-A2)") (class "Default")
      (node (ref "D3") (pin "A") (pinfunction "A_A") (pintype "passive"))
      (node (ref "RA1") (pin "8") (pinfunction "A2_8") (pintype "passive"))
    )
    (net (code "58") (name "Net-(RA1-B2)") (class "Default")
      (node (ref "D4") (pin "A") (pinfunction "A_A") (pintype "passive"))
      (node (ref "RA1") (pin "7") (pinfunction "B2_7") (pintype "passive"))
    )
    (net (code "59") (name "Net-(RA1-C2)") (class "Default")
      (node (ref "D5") (pin "A") (pinfunction "A_A") (pintype "passive"))
      (node (ref "RA1") (pin "6") (pinfunction "C2_6") (pintype "passive"))
    )
    (net (code "60") (name "Net-(RA1-D2)") (class "Default")
      (node (ref "D6") (pin "A") (pinfunction "A_A") (pintype "passive"))
      (node (ref "RA1") (pin "5") (pinfunction "D2_5") (pintype "passive"))
    )
    (net (code "61") (name "Net-(RA4-A2)") (class "Default")
      (node (ref "J6") (pin "6") (pinfunction "6_6") (pintype "bidirectional"))
      (node (ref "Q5") (pin "D1") (pinfunction "D_D1") (pintype "passive"))
      (node (ref "Q5") (pin "D2") (pinfunction "D_D2") (pintype "passive"))
      (node (ref "Q5") (pin "D3") (pinfunction "D_D3") (pintype "passive"))
      (node (ref "Q5") (pin "D4") (pinfunction "D_D4") (pintype "passive"))
      (node (ref "Q5") (pin "DPAD") (pinfunction "D_DPAD") (pintype "passive"))
      (node (ref "RA4") (pin "8") (pinfunction "A2_8") (pintype "passive"))
    )
    (net (code "62") (name "Net-(RA4-B2)") (class "Default")
      (node (ref "J6") (pin "5") (pinfunction "5_5") (pintype "bidirectional"))
      (node (ref "Q6") (pin "D1") (pinfunction "D_D1") (pintype "passive"))
      (node (ref "Q6") (pin "D2") (pinfunction "D_D2") (pintype "passive"))
      (node (ref "Q6") (pin "D3") (pinfunction "D_D3") (pintype "passive"))
      (node (ref "Q6") (pin "D4") (pinfunction "D_D4") (pintype "passive"))
      (node (ref "Q6") (pin "DPAD") (pinfunction "D_DPAD") (pintype "passive"))
      (node (ref "RA4") (pin "7") (pinfunction "B2_7") (pintype "passive"))
    )
    (net (code "63") (name "Net-(RA4-C2)") (class "Default")
      (node (ref "J6") (pin "4") (pinfunction "4_4") (pintype "bidirectional"))
      (node (ref "Q4") (pin "D1") (pinfunction "D_D1") (pintype "passive"))
      (node (ref "Q4") (pin "D2") (pinfunction "D_D2") (pintype "passive"))
      (node (ref "Q4") (pin "D3") (pinfunction "D_D3") (pintype "passive"))
      (node (ref "Q4") (pin "D4") (pinfunction "D_D4") (pintype "passive"))
      (node (ref "Q4") (pin "DPAD") (pinfunction "D_DPAD") (pintype "passive"))
      (node (ref "RA4") (pin "6") (pinfunction "C2_6") (pintype "passive"))
    )
    (net (code "64") (name "Net-(RA4-D2)") (class "Default")
      (node (ref "J6") (pin "3") (pinfunction "3_3") (pintype "bidirectional"))
      (node (ref "Q7") (pin "D1") (pinfunction "D_D1") (pintype "passive"))
      (node (ref "Q7") (pin "D2") (pinfunction "D_D2") (pintype "passive"))
      (node (ref "Q7") (pin "D3") (pinfunction "D_D3") (pintype "passive"))
      (node (ref "Q7") (pin "D4") (pinfunction "D_D4") (pintype "passive"))
      (node (ref "Q7") (pin "DPAD") (pinfunction "D_DPAD") (pintype "passive"))
      (node (ref "RA4") (pin "5") (pinfunction "D2_5") (pintype "passive"))
    )
    (net (code "65") (name "Net-(RA5-A2)") (class "Default")
      (node (ref "D7") (pin "A") (pinfunction "A_A") (pintype "passive"))
      (node (ref "RA5") (pin "8") (pinfunction "A2_8") (pintype "passive"))
    )
    (net (code "66") (name "Net-(RA5-B2)") (class "Default")
      (node (ref "D8") (pin "A") (pinfunction "A_A") (pintype "passive"))
      (node (ref "RA5") (pin "7") (pinfunction "B2_7") (pintype "passive"))
    )
    (net (code "67") (name "Net-(RA5-C2)") (class "Default")
      (node (ref "D9") (pin "A") (pinfunction "A_A") (pintype "passive"))
      (node (ref "RA5") (pin "6") (pinfunction "C2_6") (pintype "passive"))
    )
    (net (code "68") (name "Net-(RA5-D2)") (class "Default")
      (node (ref "D10") (pin "A") (pinfunction "A_A") (pintype "passive"))
      (node (ref "RA5") (pin "5") (pinfunction "D2_5") (pintype "passive"))
    )
    (net (code "69") (name "Net-(SG1-1)") (class "Default")
      (node (ref "Q1") (pin "D1") (pinfunction "D_D1") (pintype "passive"))
      (node (ref "Q1") (pin "D2") (pinfunction "D_D2") (pintype "passive"))
      (node (ref "Q1") (pin "D3") (pinfunction "D_D3") (pintype "passive"))
      (node (ref "Q1") (pin "D4") (pinfunction "D_D4") (pintype "passive"))
      (node (ref "Q1") (pin "DPAD") (pinfunction "D_DPAD") (pintype "passive"))
      (node (ref "SG1") (pin "+") (pinfunction "1_+") (pintype "passive"))
    )
    (net (code "70") (name "Net-(U5-C1)") (class "Default")
      (node (ref "C12") (pin "1") (pinfunction "1_1") (pintype "passive"))
      (node (ref "U5") (pin "6") (pinfunction "C1_6") (pintype "passive"))
    )
    (net (code "71") (name "Net-(U5-SETC_C2)") (class "Default")
      (node (ref "C10") (pin "1") (pinfunction "1_1") (pintype "passive"))
      (node (ref "U5") (pin "13") (pinfunction "SETC_C2_13") (pintype "passive"))
    )
    (net (code "72") (name "Net-(U5-SETP_C2)") (class "Default")
      (node (ref "C10") (pin "2") (pinfunction "2_2") (pintype "passive"))
      (node (ref "U5") (pin "12") (pinfunction "SETP_C2_12") (pintype "passive"))
    )
    (net (code "73") (name "unconnected-(J2-5V-Pad5V@1)") (class "Default")
      (node (ref "J2") (pin "5V@1") (pinfunction "5V_5V@1") (pintype "bidirectional"))
    )
    (net (code "74") (name "unconnected-(J2-5V-Pad5V@2)") (class "Default")
      (node (ref "J2") (pin "5V@2") (pinfunction "5V_5V@2") (pintype "bidirectional"))
    )
    (net (code "75") (name "unconnected-(J2-14(TX3)-Pad14)") (class "Default")
      (node (ref "J2") (pin "14") (pinfunction "14(TX3)_14") (pintype "bidirectional"))
    )
    (net (code "76") (name "unconnected-(J2-15(RX3)-Pad15)") (class "Default")
      (node (ref "J2") (pin "15") (pinfunction "15(RX3)_15") (pintype "bidirectional"))
    )
    (net (code "77") (name "unconnected-(J2-Pad2)") (class "Default")
      (node (ref "J2") (pin "2") (pinfunction "2_2") (pintype "bidirectional"))
    )
    (net (code "78") (name "unconnected-(J2-Pad3)") (class "Default")
      (node (ref "J2") (pin "3") (pinfunction "3_3") (pintype "bidirectional"))
    )
    (net (code "79") (name "unconnected-(J2-Pad3.3V)") (class "Default")
      (node (ref "J2") (pin "3.3V") (pinfunction "3.3V_3.3V") (pintype "bidirectional"))
    )
    (net (code "80") (name "unconnected-(J2-Pad4)") (class "Default")
      (node (ref "J2") (pin "4") (pinfunction "4_4") (pintype "bidirectional"))
    )
    (net (code "81") (name "unconnected-(J2-Pad5)") (class "Default")
      (node (ref "J2") (pin "5") (pinfunction "5_5") (pintype "bidirectional"))
    )
    (net (code "82") (name "unconnected-(J2-Pad6)") (class "Default")
      (node (ref "J2") (pin "6") (pinfunction "6_6") (pintype "bidirectional"))
    )
    (net (code "83") (name "unconnected-(J2-Pad7)") (class "Default")
      (node (ref "J2") (pin "7") (pinfunction "7_7") (pintype "bidirectional"))
    )
    (net (code "84") (name "unconnected-(J2-Pad9)") (class "Default")
      (node (ref "J2") (pin "9") (pinfunction "9_9") (pintype "bidirectional"))
    )
    (net (code "85") (name "unconnected-(J2-Pad10)") (class "Default")
      (node (ref "J2") (pin "10") (pinfunction "10_10") (pintype "bidirectional"))
    )
    (net (code "86") (name "unconnected-(J2-Pad11)") (class "Default")
      (node (ref "J2") (pin "11") (pinfunction "11_11") (pintype "bidirectional"))
    )
    (net (code "87") (name "unconnected-(J2-Pad12)") (class "Default")
      (node (ref "J2") (pin "12") (pinfunction "12_12") (pintype "bidirectional"))
    )
    (net (code "88") (name "unconnected-(J2-Pad22)") (class "Default")
      (node (ref "J2") (pin "22") (pinfunction "22_22") (pintype "bidirectional"))
    )
    (net (code "89") (name "unconnected-(J2-Pad23)") (class "Default")
      (node (ref "J2") (pin "23") (pinfunction "23_23") (pintype "bidirectional"))
    )
    (net (code "90") (name "unconnected-(J2-Pad24)") (class "Default")
      (node (ref "J2") (pin "24") (pinfunction "24_24") (pintype "bidirectional"))
    )
    (net (code "91") (name "unconnected-(J2-Pad25)") (class "Default")
      (node (ref "J2") (pin "25") (pinfunction "25_25") (pintype "bidirectional"))
    )
    (net (code "92") (name "unconnected-(J2-Pad26)") (class "Default")
      (node (ref "J2") (pin "26") (pinfunction "26_26") (pintype "bidirectional"))
    )
    (net (code "93") (name "unconnected-(J2-Pad27)") (class "Default")
      (node (ref "J2") (pin "27") (pinfunction "27_27") (pintype "bidirectional"))
    )
    (net (code "94") (name "unconnected-(J2-Pad28)") (class "Default")
      (node (ref "J2") (pin "28") (pinfunction "28_28") (pintype "bidirectional"))
    )
    (net (code "95") (name "unconnected-(J2-Pad29)") (class "Default")
      (node (ref "J2") (pin "29") (pinfunction "29_29") (pintype "bidirectional"))
    )
    (net (code "96") (name "unconnected-(J2-Pad30)") (class "Default")
      (node (ref "J2") (pin "30") (pinfunction "30_30") (pintype "bidirectional"))
    )
    (net (code "97") (name "unconnected-(J2-Pad31)") (class "Default")
      (node (ref "J2") (pin "31") (pinfunction "31_31") (pintype "bidirectional"))
    )
    (net (code "98") (name "unconnected-(J2-Pad32)") (class "Default")
      (node (ref "J2") (pin "32") (pinfunction "32_32") (pintype "bidirectional"))
    )
    (net (code "99") (name "unconnected-(J2-Pad33)") (class "Default")
      (node (ref "J2") (pin "33") (pinfunction "33_33") (pintype "bidirectional"))
    )
    (net (code "100") (name "unconnected-(J2-Pad34)") (class "Default")
      (node (ref "J2") (pin "34") (pinfunction "34_34") (pintype "bidirectional"))
    )
    (net (code "101") (name "unconnected-(J2-Pad35)") (class "Default")
      (node (ref "J2") (pin "35") (pinfunction "35_35") (pintype "bidirectional"))
    )
    (net (code "102") (name "unconnected-(J2-Pad36)") (class "Default")
      (node (ref "J2") (pin "36") (pinfunction "36_36") (pintype "bidirectional"))
    )
    (net (code "103") (name "unconnected-(J2-Pad37)") (class "Default")
      (node (ref "J2") (pin "37") (pinfunction "37_37") (pintype "bidirectional"))
    )
    (net (code "104") (name "unconnected-(J2-Pad38)") (class "Default")
      (node (ref "J2") (pin "38") (pinfunction "38_38") (pintype "bidirectional"))
    )
    (net (code "105") (name "unconnected-(J2-Pad39)") (class "Default")
      (node (ref "J2") (pin "39") (pinfunction "39_39") (pintype "bidirectional"))
    )
    (net (code "106") (name "unconnected-(J2-Pad40)") (class "Default")
      (node (ref "J2") (pin "40") (pinfunction "40_40") (pintype "bidirectional"))
    )
    (net (code "107") (name "unconnected-(J2-Pad41)") (class "Default")
      (node (ref "J2") (pin "41") (pinfunction "41_41") (pintype "bidirectional"))
    )
    (net (code "108") (name "unconnected-(J2-Pad46)") (class "Default")
      (node (ref "J2") (pin "46") (pinfunction "46_46") (pintype "bidirectional"))
    )
    (net (code "109") (name "unconnected-(J2-Pad47)") (class "Default")
      (node (ref "J2") (pin "47") (pinfunction "47_47") (pintype "bidirectional"))
    )
    (net (code "110") (name "unconnected-(J2-Pad49)") (class "Default")
      (node (ref "J2") (pin "49") (pinfunction "49_49") (pintype "bidirectional"))
    )
    (net (code "111") (name "unconnected-(J2-Pad53)") (class "Default")
      (node (ref "J2") (pin "53") (pinfunction "53_53") (pintype "bidirectional"))
    )
    (net (code "112") (name "unconnected-(J2-PadAREF)") (class "Default")
      (node (ref "J2") (pin "AREF") (pinfunction "AREF_AREF") (pintype "bidirectional"))
    )
    (net (code "113") (name "unconnected-(J2-PadSCL1)") (class "Default")
      (node (ref "J2") (pin "SCL1") (pinfunction "SCL1_SCL1") (pintype "bidirectional"))
    )
    (net (code "114") (name "unconnected-(J2-PadSDA1)") (class "Default")
      (node (ref "J2") (pin "SDA1") (pinfunction "SDA1_SDA1") (pintype "bidirectional"))
    )
    (net (code "115") (name "unconnected-(J3-AD0{slash}DIO0-Pad20)") (class "Default")
      (node (ref "J3") (pin "20") (pinfunction "AD0/DIO0_20") (pintype "bidirectional"))
    )
    (net (code "116") (name "unconnected-(J3-AD1{slash}DIO1-Pad19)") (class "Default")
      (node (ref "J3") (pin "19") (pinfunction "AD1/DIO1_19") (pintype "bidirectional"))
    )
    (net (code "117") (name "unconnected-(J3-AD2{slash}DIO2-Pad18)") (class "Default")
      (node (ref "J3") (pin "18") (pinfunction "AD2/DIO2_18") (pintype "bidirectional"))
    )
    (net (code "118") (name "unconnected-(J3-AD3{slash}DIO3-Pad17)") (class "Default")
      (node (ref "J3") (pin "17") (pinfunction "AD3/DIO3_17") (pintype "bidirectional"))
    )
    (net (code "119") (name "unconnected-(J3-AD4{slash}DIO4-Pad11)") (class "Default")
      (node (ref "J3") (pin "11") (pinfunction "AD4/DIO4_11") (pintype "bidirectional"))
    )
    (net (code "120") (name "unconnected-(J3-ASC{slash}AD5{slash}DIO5-Pad15)") (class "Default")
      (node (ref "J3") (pin "15") (pinfunction "ASC/AD5/DIO5_15") (pintype "bidirectional"))
    )
    (net (code "121") (name "unconnected-(J3-CTS{slash}DIO7-Pad12)") (class "Default")
      (node (ref "J3") (pin "12") (pinfunction "CTS/DIO7_12") (pintype "bidirectional"))
    )
    (net (code "122") (name "unconnected-(J3-DO8-Pad4)") (class "Default")
      (node (ref "J3") (pin "4") (pinfunction "DO8_4") (pintype "output"))
    )
    (net (code "123") (name "unconnected-(J3-DTR{slash}DI8-Pad9)") (class "Default")
      (node (ref "J3") (pin "9") (pinfunction "DTR/DI8_9") (pintype "input"))
    )
    (net (code "124") (name "unconnected-(J3-ON{slash}SLEEP-Pad13)") (class "Default")
      (node (ref "J3") (pin "13") (pinfunction "ON/SLEEP_13") (pintype "output"))
    )
    (net (code "125") (name "unconnected-(J3-PWM1-Pad7)") (class "Default")
      (node (ref "J3") (pin "7") (pinfunction "PWM1_7") (pintype "output"))
    )
    (net (code "126") (name "unconnected-(J3-RESERVED-Pad8)") (class "Default")
      (node (ref "J3") (pin "8") (pinfunction "RESERVED_8") (pintype "no_connect"))
    )
    (net (code "127") (name "unconnected-(J3-RESET-Pad5)") (class "Default")
      (node (ref "J3") (pin "5") (pinfunction "RESET_5") (pintype "input"))
    )
    (net (code "128") (name "unconnected-(J3-RTS{slash}AD6{slash}DIO6-Pad16)") (class "Default")
      (node (ref "J3") (pin "16") (pinfunction "RTS/AD6/DIO6_16") (pintype "bidirectional"))
    )
    (net (code "129") (name "unconnected-(J3-VREF-Pad14)") (class "Default")
      (node (ref "J3") (pin "14") (pinfunction "VREF_14") (pintype "input"))
    )
    (net (code "130") (name "unconnected-(J4-DAT1-Pad8)") (class "Default")
      (node (ref "J4") (pin "8") (pinfunction "DAT1_8") (pintype "bidirectional"))
    )
    (net (code "131") (name "unconnected-(J4-DAT2-Pad1)") (class "Default")
      (node (ref "J4") (pin "1") (pinfunction "DAT2_1") (pintype "bidirectional"))
    )
    (net (code "132") (name "unconnected-(U3-1PPS-PadP$13)") (class "Default")
      (node (ref "U3") (pin "P$13") (pinfunction "1PPS_P$13") (pintype "bidirectional"))
    )
    (net (code "133") (name "unconnected-(U3-NC-PadP$6)") (class "Default")
      (node (ref "U3") (pin "P$6") (pinfunction "NC_P$6") (pintype "bidirectional"))
    )
    (net (code "134") (name "unconnected-(U3-NC-PadP$7)") (class "Default")
      (node (ref "U3") (pin "P$7") (pinfunction "NC_P$7") (pintype "bidirectional"))
    )
    (net (code "135") (name "unconnected-(U3-NC-PadP$15)") (class "Default")
      (node (ref "U3") (pin "P$15") (pinfunction "NC_P$15") (pintype "bidirectional"))
    )
    (net (code "136") (name "unconnected-(U3-NC-PadP$16)") (class "Default")
      (node (ref "U3") (pin "P$16") (pinfunction "NC_P$16") (pintype "bidirectional"))
    )
    (net (code "137") (name "unconnected-(U3-NC-PadP$17)") (class "Default")
      (node (ref "U3") (pin "P$17") (pinfunction "NC_P$17") (pintype "bidirectional"))
    )
    (net (code "138") (name "unconnected-(U3-NC-PadP$18)") (class "Default")
      (node (ref "U3") (pin "P$18") (pinfunction "NC_P$18") (pintype "bidirectional"))
    )
    (net (code "139") (name "unconnected-(U3-NC-PadP$20)") (class "Default")
      (node (ref "U3") (pin "P$20") (pinfunction "NC_P$20") (pintype "bidirectional"))
    )
    (net (code "140") (name "unconnected-(U3-NRESET-PadP$2)") (class "Default")
      (node (ref "U3") (pin "P$2") (pinfunction "NRESET_P$2") (pintype "bidirectional"))
    )
    (net (code "141") (name "unconnected-(U3-RTCM-PadP$14)") (class "Default")
      (node (ref "U3") (pin "P$14") (pinfunction "RTCM_P$14") (pintype "bidirectional"))
    )
    (net (code "142") (name "unconnected-(U3-VBACKUP-PadP$4)") (class "Default")
      (node (ref "U3") (pin "P$4") (pinfunction "VBACKUP_P$4") (pintype "bidirectional"))
    )
    (net (code "143") (name "unconnected-(U4-CSB-Pad1)") (class "Default")
      (node (ref "U4") (pin "1") (pinfunction "CSB_1") (pintype "no_connect"))
    )
    (net (code "144") (name "unconnected-(U4-SDO-Pad4)") (class "Default")
      (node (ref "U4") (pin "4") (pinfunction "SDO_4") (pintype "no_connect"))
    )
    (net (code "145") (name "unconnected-(U5-DRDY-Pad9)") (class "Default")
      (node (ref "U5") (pin "9") (pinfunction "DRDY_9") (pintype "bidirectional"))
    )
    (net (code "146") (name "unconnected-(U5-INT1-Pad5)") (class "Default")
      (node (ref "U5") (pin "5") (pinfunction "INT1_5") (pintype "bidirectional"))
    )
    (net (code "147") (name "unconnected-(U5-INT2-Pad4)") (class "Default")
      (node (ref "U5") (pin "4") (pinfunction "INT2_4") (pintype "bidirectional"))
    )
    (net (code "148") (name "unconnected-(U5-NC-Pad8)") (class "Default")
      (node (ref "U5") (pin "8") (pinfunction "NC_8") (pintype "no_connect"))
    )
    (net (code "149") (name "unconnected-(U6-CS-PadP$5)") (class "Default")
      (node (ref "U6") (pin "P$5") (pinfunction "CS_P$5") (pintype "input"))
    )
    (net (code "150") (name "unconnected-(U6-INT1-PadP$7)") (class "Default")
      (node (ref "U6") (pin "P$7") (pinfunction "INT1_P$7") (pintype "bidirectional"))
    )
    (net (code "151") (name "unconnected-(U6-INT2-PadP$6)") (class "Default")
      (node (ref "U6") (pin "P$6") (pinfunction "INT2_P$6") (pintype "bidirectional"))
    )
    (net (code "152") (name "unconnected-(U6-SDO-PadP$4)") (class "Default")
      (node (ref "U6") (pin "P$4") (pinfunction "SDO_P$4") (pintype "bidirectional"))
    )
    (net (code "153") (name "unconnected-(U7-NC-Pad8)") (class "Default")
      (node (ref "U7") (pin "8") (pinfunction "NC_8") (pintype "no_connect"))
    )
    (net (code "154") (name "unconnected-(U7-NC-Pad9)") (class "Default")
      (node (ref "U7") (pin "9") (pinfunction "NC_9") (pintype "no_connect"))
    )
    (net (code "155") (name "unconnected-(U7-NC-Pad10)") (class "Default")
      (node (ref "U7") (pin "10") (pinfunction "NC_10") (pintype "no_connect"))
    )
    (net (code "156") (name "unconnected-(U7-NC-Pad11)") (class "Default")
      (node (ref "U7") (pin "11") (pinfunction "NC_11") (pintype "no_connect"))
    )
    (net (code "157") (name "unconnected-(U7-NC-Pad12)") (class "Default")
      (node (ref "U7") (pin "12") (pinfunction "NC_12") (pintype "no_connect"))
    )
    (net (code "158") (name "unconnected-(U7-NC-Pad13)") (class "Default")
      (node (ref "U7") (pin "13") (pinfunction "NC_13") (pintype "no_connect"))
    )
    (net (code "159") (name "unconnected-(U7-RES-Pad1)") (class "Default")
      (node (ref "U7") (pin "1") (pinfunction "RES_1") (pintype "no_connect"))
    )
    (net (code "160") (name "unconnected-(U7-RES-Pad3)") (class "Default")
      (node (ref "U7") (pin "3") (pinfunction "RES_3") (pintype "no_connect"))
    )
    (net (code "161") (name "unconnected-(U7-ST-Pad2)") (class "Default")
      (node (ref "U7") (pin "2") (pinfunction "ST_2") (pintype "input"))
    )
  )
)
